# core_corin.net
KiCad netlist of a schematic drawn in Altium Designer
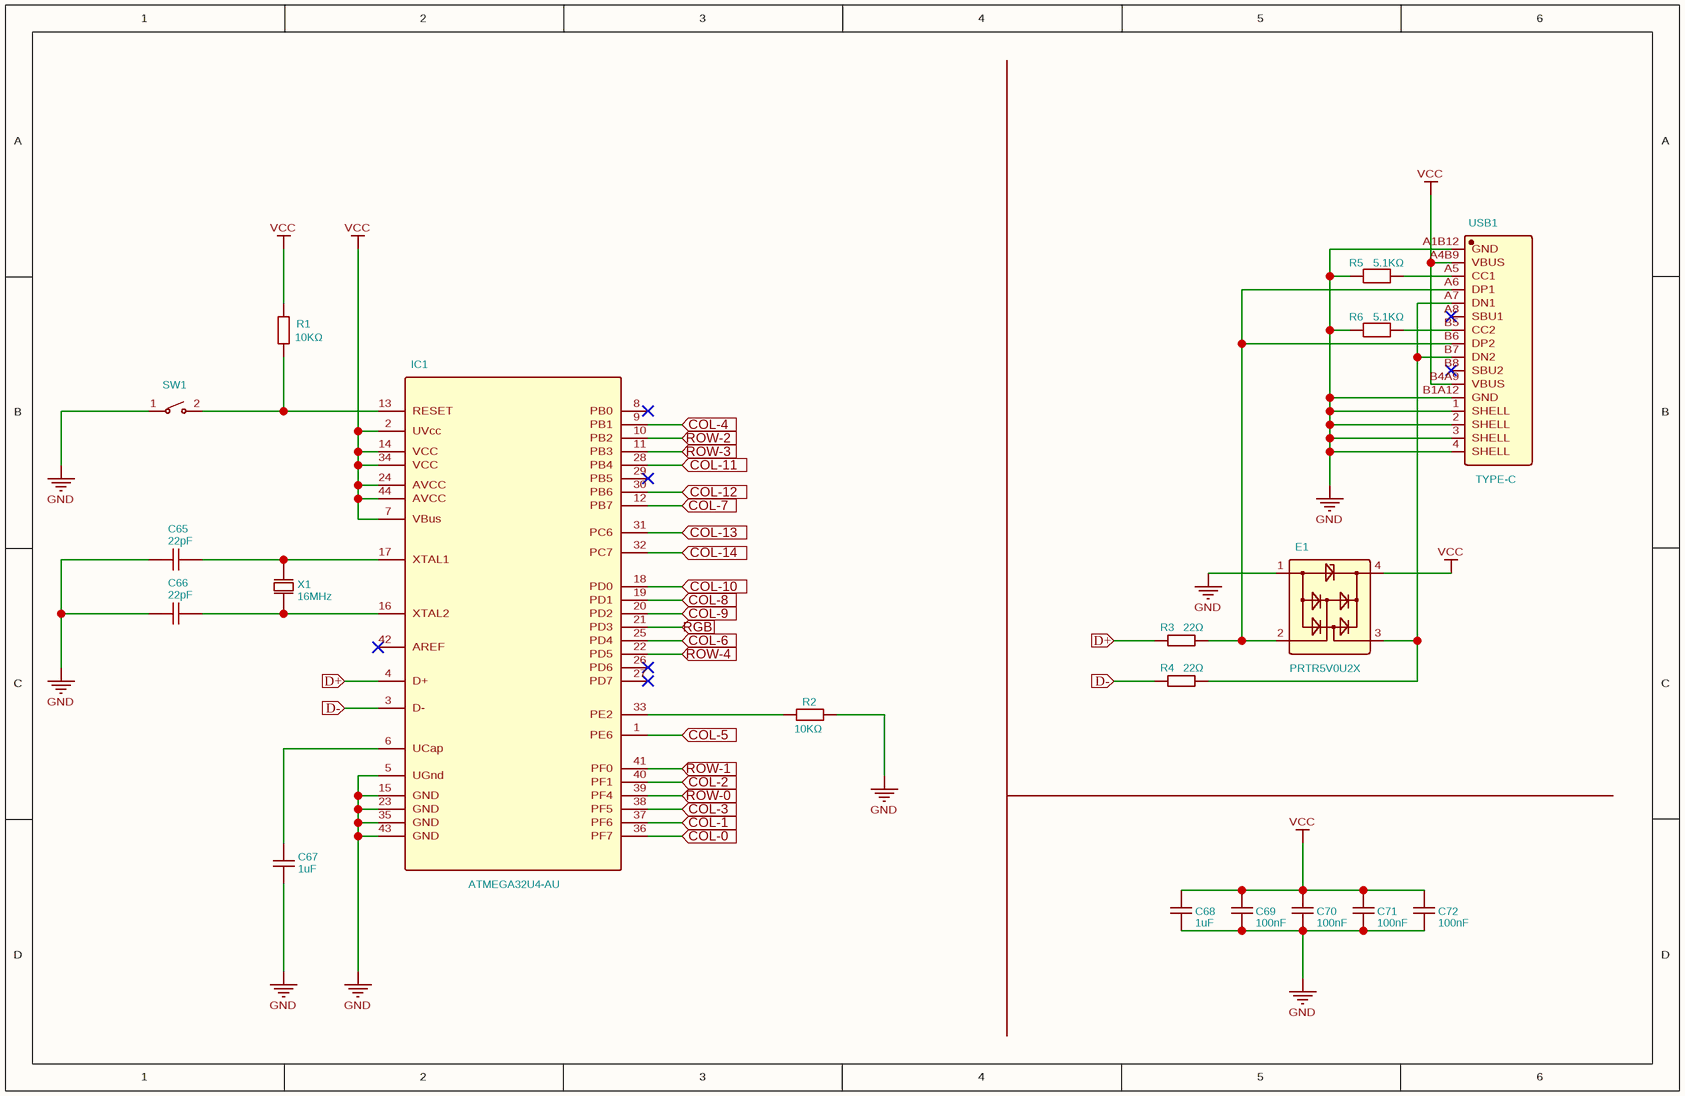
[diagram p0: core_corin.schdoc]

(export (version "E")
  (design (tool "Eeschema 10.0.6"))
  (components
    (comp (ref "C65")
      (value "22pF")
      (fields
        (field (name "BOM_MANUFACTURER PART") "CL10C220JB81PNC")
        (field (name "BOM_SUPPLIER PART") "C170132")
        (field (name "CONTRIBUTOR") "LCSC")
      )
      (libsource (lib "altium-import") (part "root_0_22pF_"))
    )
    (comp (ref "C66")
      (value "22pF")
      (fields
        (field (name "BOM_MANUFACTURER PART") "CL10C220JB81PNC")
        (field (name "BOM_SUPPLIER PART") "C170132")
        (field (name "CONTRIBUTOR") "LCSC")
      )
      (libsource (lib "altium-import") (part "root_0_22pF_"))
    )
    (comp (ref "C67")
      (value "1uF")
      (fields
        (field (name "BOM_MANUFACTURER PART") "CL10A105KB8NNNC")
        (field (name "BOM_SUPPLIER PART") "C15849")
      )
      (libsource (lib "altium-import") (part "root_1_1uF_"))
    )
    (comp (ref "C68")
      (value "1uF")
      (fields
        (field (name "BOM_MANUFACTURER PART") "CL10A105KB8NNNC")
        (field (name "BOM_SUPPLIER PART") "C15849")
      )
      (libsource (lib "altium-import") (part "root_1_1uF_"))
    )
    (comp (ref "C69")
      (value "100nF")
      (fields
        (field (name "BOM_MANUFACTURER PART") "CC0805KRX7R9BB104")
        (field (name "BOM_SUPPLIER PART") "C49678")
      )
      (libsource (lib "altium-import") (part "root_1_100nF_"))
    )
    (comp (ref "C70")
      (value "100nF")
      (fields
        (field (name "BOM_MANUFACTURER PART") "CC0805KRX7R9BB104")
        (field (name "BOM_SUPPLIER PART") "C49678")
      )
      (libsource (lib "altium-import") (part "root_1_100nF_"))
    )
    (comp (ref "C71")
      (value "100nF")
      (fields
        (field (name "BOM_MANUFACTURER PART") "CC0805KRX7R9BB104")
        (field (name "BOM_SUPPLIER PART") "C49678")
      )
      (libsource (lib "altium-import") (part "root_1_100nF_"))
    )
    (comp (ref "C72")
      (value "100nF")
      (fields
        (field (name "BOM_MANUFACTURER PART") "CC0805KRX7R9BB104")
        (field (name "BOM_SUPPLIER PART") "C49678")
      )
      (libsource (lib "altium-import") (part "root_1_100nF_"))
    )
    (comp (ref "E1")
      (value "PRTR5V0U2X")
      (fields (field (name "BOM_SUPPLIER PART") "C12333") (field (name "CONTRIBUTOR") "Longnald"))
      (libsource (lib "altium-import") (part "root_0_PRTR5V0U2X_"))
    )
    (comp (ref "IC1")
      (value "ATMEGA32U4-AU")
      (fields (field (name "BOM_SUPPLIER PART") "C44854") (field (name "CONTRIBUTOR") "亓荒"))
      (libsource (lib "altium-import") (part "root_0_ATMEGA32U4-AU_"))
    )
    (comp (ref "R1")
      (value "10KΩ")
      (fields
        (field (name "BOM_SUPPLIER PART") "C167144")
        (field (name "BOM_MANUFACTURER PART") "0603WAD1002T5E")
        (field (name "CONTRIBUTOR") "LCSC")
      )
      (libsource (lib "altium-import") (part "root_1_10KΩ_"))
    )
    (comp (ref "R2")
      (value "10KΩ")
      (fields
        (field (name "BOM_SUPPLIER PART") "C167144")
        (field (name "BOM_MANUFACTURER PART") "0603WAD1002T5E")
        (field (name "CONTRIBUTOR") "LCSC")
      )
      (libsource (lib "altium-import") (part "root_2_10KΩ_"))
    )
    (comp (ref "R3")
      (value "22Ω")
      (fields
        (field (name "BOM_MANUFACTURER PART") "0603WAF220JT5E")
        (field (name "BOM_SUPPLIER PART") "C23345")
      )
      (libsource (lib "altium-import") (part "root_0_22Ω_"))
    )
    (comp (ref "R4")
      (value "22Ω")
      (fields
        (field (name "BOM_MANUFACTURER PART") "0603WAF220JT5E")
        (field (name "BOM_SUPPLIER PART") "C23345")
      )
      (libsource (lib "altium-import") (part "root_0_22Ω_"))
    )
    (comp (ref "R5")
      (value "5.1KΩ")
      (fields
        (field (name "BOM_SUPPLIER PART") "C416158")
        (field (name "BOM_MANUFACTURER PART") "CR-05JL7---5K1")
        (field (name "CONTRIBUTOR") "LCSC")
      )
      (libsource (lib "altium-import") (part "root_0_5.1KΩ_"))
    )
    (comp (ref "R6")
      (value "5.1KΩ")
      (fields
        (field (name "BOM_SUPPLIER PART") "C416158")
        (field (name "BOM_MANUFACTURER PART") "CR-05JL7---5K1")
        (field (name "CONTRIBUTOR") "LCSC")
      )
      (libsource (lib "altium-import") (part "root_0_5.1KΩ_"))
    )
    (comp (ref "SW1")
      (value "TS-1088R-02026")
      (fields (field (name "BOM_SUPPLIER PART") "C455280") (field (name "CONTRIBUTOR") "LCSC"))
      (libsource (lib "altium-import") (part "root_0_TS-1088R-02026_"))
    )
    (comp (ref "USB1")
      (value "TYPE-C")
      (fields
        (field (name "BOM_SUPPLIER PART") "C393939")
        (field (name "BOM_MANUFACTURER PART") "TYPE-C16PIN")
        (field (name "CONTRIBUTOR") "Longnald")
      )
      (libsource (lib "altium-import") (part "root_0_TYPE-C_"))
    )
    (comp (ref "X1")
      (value "16MHz")
      (fields
        (field (name "BOM_SUPPLIER PART") "C242221")
        (field (name "BOM_MANUFACTURER PART") "XSHEELNANF-16MHZ")
        (field (name "CONTRIBUTOR") "LCSC")
      )
      (libsource (lib "altium-import") (part "root_1_16MHz_"))
    )
  )
  (nets
    (net (code "1") (name "/COL-0") (class "Default")
      (node (ref "IC1") (pin "36") (pinfunction "PF7_36") (pintype "passive"))
    )
    (net (code "2") (name "/COL-1") (class "Default")
      (node (ref "IC1") (pin "37") (pinfunction "PF6_37") (pintype "passive"))
    )
    (net (code "3") (name "/COL-2") (class "Default")
      (node (ref "IC1") (pin "40") (pinfunction "PF1_40") (pintype "passive"))
    )
    (net (code "4") (name "/COL-3") (class "Default")
      (node (ref "IC1") (pin "38") (pinfunction "PF5_38") (pintype "passive"))
    )
    (net (code "5") (name "/COL-4") (class "Default")
      (node (ref "IC1") (pin "9") (pinfunction "PB1_9") (pintype "passive"))
    )
    (net (code "6") (name "/COL-5") (class "Default")
      (node (ref "IC1") (pin "1") (pinfunction "PE6_1") (pintype "passive"))
    )
    (net (code "7") (name "/COL-6") (class "Default")
      (node (ref "IC1") (pin "25") (pinfunction "PD4_25") (pintype "passive"))
    )
    (net (code "8") (name "/COL-7") (class "Default")
      (node (ref "IC1") (pin "12") (pinfunction "PB7_12") (pintype "passive"))
    )
    (net (code "9") (name "/COL-8") (class "Default")
      (node (ref "IC1") (pin "19") (pinfunction "PD1_19") (pintype "passive"))
    )
    (net (code "10") (name "/COL-9") (class "Default")
      (node (ref "IC1") (pin "20") (pinfunction "PD2_20") (pintype "passive"))
    )
    (net (code "11") (name "/COL-10") (class "Default")
      (node (ref "IC1") (pin "18") (pinfunction "PD0_18") (pintype "passive"))
    )
    (net (code "12") (name "/COL-11") (class "Default")
      (node (ref "IC1") (pin "28") (pinfunction "PB4_28") (pintype "passive"))
    )
    (net (code "13") (name "/COL-12") (class "Default")
      (node (ref "IC1") (pin "30") (pinfunction "PB6_30") (pintype "passive"))
    )
    (net (code "14") (name "/COL-13") (class "Default")
      (node (ref "IC1") (pin "31") (pinfunction "PC6_31") (pintype "passive"))
    )
    (net (code "15") (name "/COL-14") (class "Default")
      (node (ref "IC1") (pin "32") (pinfunction "PC7_32") (pintype "passive"))
    )
    (net (code "16") (name "/D+") (class "Default")
      (node (ref "IC1") (pin "4") (pinfunction "D+_4") (pintype "passive"))
      (node (ref "R3") (pin "1") (pinfunction "1_1") (pintype "passive"))
    )
    (net (code "17") (name "/D-") (class "Default")
      (node (ref "IC1") (pin "3") (pinfunction "D-_3") (pintype "passive"))
      (node (ref "R4") (pin "1") (pinfunction "1_1") (pintype "passive"))
    )
    (net (code "18") (name "/RGB") (class "Default")
      (node (ref "IC1") (pin "21") (pinfunction "PD3_21") (pintype "passive"))
    )
    (net (code "19") (name "/ROW-0") (class "Default")
      (node (ref "IC1") (pin "39") (pinfunction "PF4_39") (pintype "passive"))
    )
    (net (code "20") (name "/ROW-1") (class "Default")
      (node (ref "IC1") (pin "41") (pinfunction "PF0_41") (pintype "passive"))
    )
    (net (code "21") (name "/ROW-2") (class "Default")
      (node (ref "IC1") (pin "10") (pinfunction "PB2_10") (pintype "passive"))
    )
    (net (code "22") (name "/ROW-3") (class "Default")
      (node (ref "IC1") (pin "11") (pinfunction "PB3_11") (pintype "passive"))
    )
    (net (code "23") (name "/ROW-4") (class "Default")
      (node (ref "IC1") (pin "22") (pinfunction "PD5_22") (pintype "passive"))
    )
    (net (code "24") (name "GND") (class "Default")
      (node (ref "C65") (pin "2") (pinfunction "2_2") (pintype "passive"))
      (node (ref "C66") (pin "2") (pinfunction "2_2") (pintype "passive"))
      (node (ref "C67") (pin "1") (pinfunction "1_1") (pintype "passive"))
      (node (ref "C68") (pin "1") (pinfunction "1_1") (pintype "passive"))
      (node (ref "C69") (pin "1") (pinfunction "1_1") (pintype "passive"))
      (node (ref "C70") (pin "1") (pinfunction "1_1") (pintype "passive"))
      (node (ref "C71") (pin "1") (pinfunction "1_1") (pintype "passive"))
      (node (ref "C72") (pin "1") (pinfunction "1_1") (pintype "passive"))
      (node (ref "E1") (pin "1") (pinfunction "GND_1") (pintype "passive"))
      (node (ref "IC1") (pin "15") (pinfunction "GND_15") (pintype "passive"))
      (node (ref "IC1") (pin "23") (pinfunction "GND_23") (pintype "passive"))
      (node (ref "IC1") (pin "35") (pinfunction "GND_35") (pintype "passive"))
      (node (ref "IC1") (pin "43") (pinfunction "GND_43") (pintype "passive"))
      (node (ref "IC1") (pin "5") (pinfunction "UGnd_5") (pintype "passive"))
      (node (ref "R2") (pin "1") (pinfunction "1_1") (pintype "passive"))
      (node (ref "R5") (pin "1") (pinfunction "1_1") (pintype "passive"))
      (node (ref "R6") (pin "1") (pinfunction "1_1") (pintype "passive"))
      (node (ref "SW1") (pin "1") (pinfunction "1_1") (pintype "passive"))
      (node (ref "USB1") (pin "1") (pinfunction "SHELL_1") (pintype "passive"))
      (node (ref "USB1") (pin "2") (pinfunction "SHELL_2") (pintype "passive"))
      (node (ref "USB1") (pin "3") (pinfunction "SHELL_3") (pintype "passive"))
      (node (ref "USB1") (pin "4") (pinfunction "SHELL_4") (pintype "passive"))
      (node (ref "USB1") (pin "A1B12") (pinfunction "GND_A1B12") (pintype "passive"))
      (node (ref "USB1") (pin "B1A12") (pinfunction "GND_B1A12") (pintype "passive"))
    )
    (net (code "25") (name "Net-(E1-IO1)") (class "Default")
      (node (ref "E1") (pin "2") (pinfunction "IO1_2") (pintype "passive"))
      (node (ref "R3") (pin "2") (pinfunction "2_2") (pintype "passive"))
      (node (ref "USB1") (pin "A6") (pinfunction "DP1_A6") (pintype "passive"))
      (node (ref "USB1") (pin "B6") (pinfunction "DP2_B6") (pintype "passive"))
    )
    (net (code "26") (name "Net-(E1-IO2)") (class "Default")
      (node (ref "E1") (pin "3") (pinfunction "IO2_3") (pintype "passive"))
      (node (ref "R4") (pin "2") (pinfunction "2_2") (pintype "passive"))
      (node (ref "USB1") (pin "A7") (pinfunction "DN1_A7") (pintype "passive"))
      (node (ref "USB1") (pin "B7") (pinfunction "DN2_B7") (pintype "passive"))
    )
    (net (code "27") (name "Net-(IC1-PE2)") (class "Default")
      (node (ref "IC1") (pin "33") (pinfunction "PE2_33") (pintype "passive"))
      (node (ref "R2") (pin "2") (pinfunction "2_2") (pintype "passive"))
    )
    (net (code "28") (name "Net-(IC1-RESET)") (class "Default")
      (node (ref "IC1") (pin "13") (pinfunction "RESET_13") (pintype "passive"))
      (node (ref "R1") (pin "1") (pinfunction "1_1") (pintype "passive"))
      (node (ref "SW1") (pin "2") (pinfunction "2_2") (pintype "passive"))
    )
    (net (code "29") (name "Net-(IC1-UCap)") (class "Default")
      (node (ref "C67") (pin "2") (pinfunction "2_2") (pintype "passive"))
      (node (ref "IC1") (pin "6") (pinfunction "UCap_6") (pintype "passive"))
    )
    (net (code "30") (name "Net-(IC1-XTAL1)") (class "Default")
      (node (ref "C65") (pin "1") (pinfunction "1_1") (pintype "passive"))
      (node (ref "IC1") (pin "17") (pinfunction "XTAL1_17") (pintype "passive"))
      (node (ref "X1") (pin "2") (pinfunction "OSC2_2") (pintype "passive"))
    )
    (net (code "31") (name "Net-(IC1-XTAL2)") (class "Default")
      (node (ref "C66") (pin "1") (pinfunction "1_1") (pintype "passive"))
      (node (ref "IC1") (pin "16") (pinfunction "XTAL2_16") (pintype "passive"))
      (node (ref "X1") (pin "1") (pinfunction "OSC1_1") (pintype "passive"))
    )
    (net (code "32") (name "Net-(USB1-CC1)") (class "Default")
      (node (ref "R5") (pin "2") (pinfunction "2_2") (pintype "passive"))
      (node (ref "USB1") (pin "A5") (pinfunction "CC1_A5") (pintype "passive"))
    )
    (net (code "33") (name "Net-(USB1-CC2)") (class "Default")
      (node (ref "R6") (pin "2") (pinfunction "2_2") (pintype "passive"))
      (node (ref "USB1") (pin "B5") (pinfunction "CC2_B5") (pintype "passive"))
    )
    (net (code "34") (name "VCC") (class "Default")
      (node (ref "C68") (pin "2") (pinfunction "2_2") (pintype "passive"))
      (node (ref "C69") (pin "2") (pinfunction "2_2") (pintype "passive"))
      (node (ref "C70") (pin "2") (pinfunction "2_2") (pintype "passive"))
      (node (ref "C71") (pin "2") (pinfunction "2_2") (pintype "passive"))
      (node (ref "C72") (pin "2") (pinfunction "2_2") (pintype "passive"))
      (node (ref "E1") (pin "4") (pinfunction "VCC_4") (pintype "passive"))
      (node (ref "IC1") (pin "14") (pinfunction "VCC_14") (pintype "passive"))
      (node (ref "IC1") (pin "2") (pinfunction "UVcc_2") (pintype "passive"))
      (node (ref "IC1") (pin "24") (pinfunction "AVCC_24") (pintype "passive"))
      (node (ref "IC1") (pin "34") (pinfunction "VCC_34") (pintype "passive"))
      (node (ref "IC1") (pin "44") (pinfunction "AVCC_44") (pintype "passive"))
      (node (ref "IC1") (pin "7") (pinfunction "VBus_7") (pintype "passive"))
      (node (ref "R1") (pin "2") (pinfunction "2_2") (pintype "passive"))
      (node (ref "USB1") (pin "A4B9") (pinfunction "VBUS_A4B9") (pintype "passive"))
      (node (ref "USB1") (pin "B4A9") (pinfunction "VBUS_B4A9") (pintype "passive"))
    )
    (net (code "35") (name "unconnected-(IC1-AREF-Pad42)") (class "Default")
      (node (ref "IC1") (pin "42") (pinfunction "AREF_42") (pintype "passive+no_connect"))
    )
    (net (code "36") (name "unconnected-(IC1-PB0-Pad8)") (class "Default")
      (node (ref "IC1") (pin "8") (pinfunction "PB0_8") (pintype "passive+no_connect"))
    )
    (net (code "37") (name "unconnected-(IC1-PB5-Pad29)") (class "Default")
      (node (ref "IC1") (pin "29") (pinfunction "PB5_29") (pintype "passive+no_connect"))
    )
    (net (code "38") (name "unconnected-(IC1-PD6-Pad26)") (class "Default")
      (node (ref "IC1") (pin "26") (pinfunction "PD6_26") (pintype "passive+no_connect"))
    )
    (net (code "39") (name "unconnected-(IC1-PD7-Pad27)") (class "Default")
      (node (ref "IC1") (pin "27") (pinfunction "PD7_27") (pintype "passive+no_connect"))
    )
    (net (code "40") (name "unconnected-(USB1-SBU1-PadA8)") (class "Default")
      (node (ref "USB1") (pin "A8") (pinfunction "SBU1_A8") (pintype "passive+no_connect"))
    )
    (net (code "41") (name "unconnected-(USB1-SBU2-PadB8)") (class "Default")
      (node (ref "USB1") (pin "B8") (pinfunction "SBU2_B8") (pintype "passive+no_connect"))
    )
  )
)
